# airu-board_0.net
KiCad netlist of a schematic drawn in Altium Designer
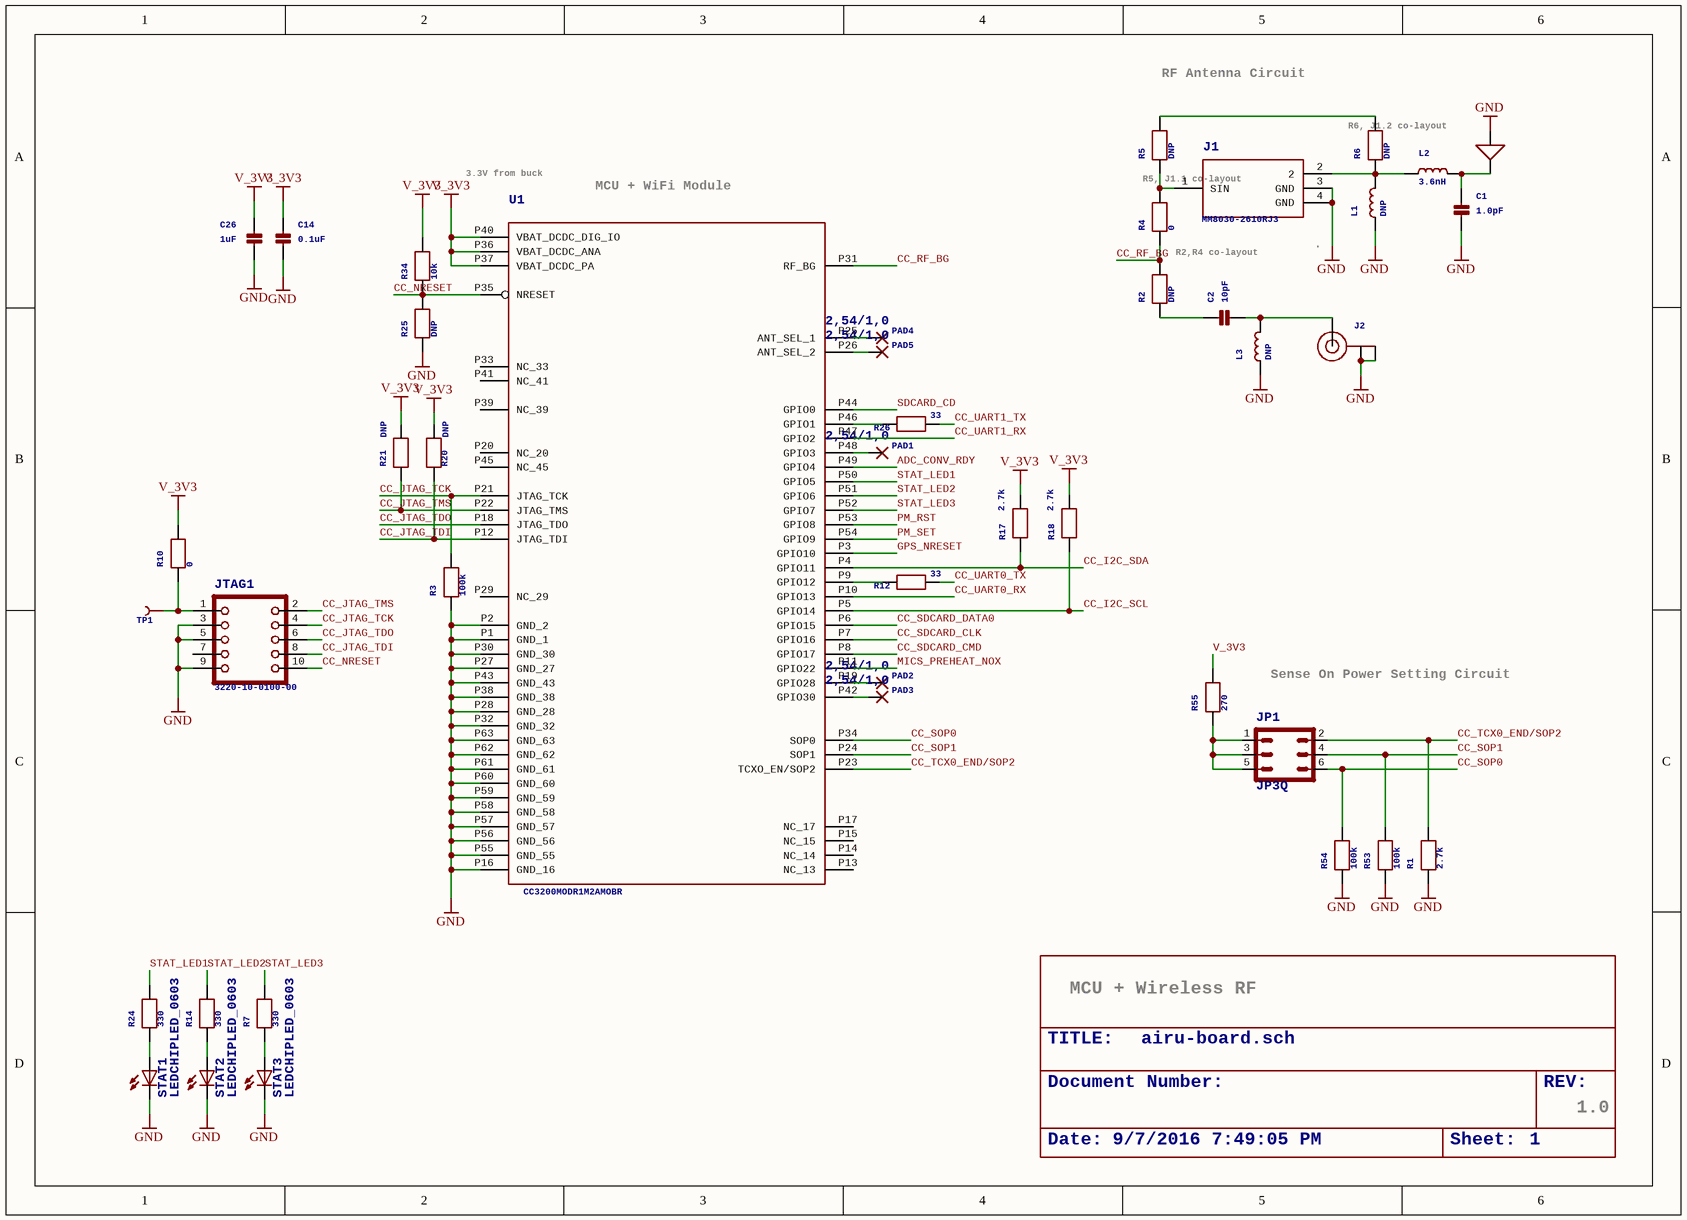
[diagram p0: airu-board_0.SchDoc]

(export (version "E")
  (design (tool "Eeschema 10.0.6"))
  (components
    (comp (ref "C1")
      (value "1.0pF")
      (footprint "0402")
      (libsource (lib "microbuilder") (part "CAP_CERAMIC0402"))
    )
    (comp (ref "C2") (value "10pF") (footprint "0402") (libsource (lib "") (part "CAP_CERAMIC0402_2")))
    (comp (ref "C14")
      (value "0.1uF")
      (footprint "0402")
      (libsource (lib "microbuilder") (part "CAP_CERAMIC0402"))
    )
    (comp (ref "C26") (value "1uF") (footprint "0402") (libsource (lib "") (part "CAP_CERAMIC0402_1")))
    (comp (ref "E1")
      (value "AH316M245001-T")
      (footprint "AH316M")
      (description "ANT BLUETOOTH W-LAN ZIGBEE WIMAX")
      (libsource (lib "yuden") (part "AH316M245001-T"))
    )
    (comp (ref "FRAME1")
      (value "FRAME_A_L")
      (description "<b>FRAME</b> A Size , 8 1/2 x 11 INCH, Landscape<p>")
      (fields
        (field (name "DATE:") "Date:")
        (field (name ">LAST_DATE_TIME") "9/7/2016 7:49:05 PM")
        (field (name "SHEET:") "Sheet:")
        (field (name ">SHEET") "1")
        (field (name "REV:") "REV:")
        (field (name "TITLE:") "TITLE:")
        (field (name "DOCUMENT NUMBER:") "Document Number:")
        (field (name ">DRAWING_NAME") "airu-board.sch")
      )
      (libsource (lib "frames") (part "FRAME_A_L"))
    )
    (comp (ref "J1")
      (value "MM8030-2610RJ3")
      (footprint "MURATA_MM8030-2610RJ3")
      (description "Conn Coaxial RCP 0Hz to 11GHz 50Ohm Solder ST SMD Gold Reel")
      (libsource (lib "MM8030-2610RJ3") (part "MM8030-2610RJ3"))
    )
    (comp (ref "J2")
      (value "U.FL-R-SMT-1(10)")
      (footprint "U.FL")
      (description "<p>U.FL Antenna Connector</p>")
      (libsource (lib "microbuilder") (part "U.FL"))
    )
    (comp (ref "JP1")
      (value "JP3Q")
      (footprint "JP3Q")
      (description "<b>JUMPER</b>")
      (libsource (lib "jumper") (part "JP3Q"))
    )
    (comp (ref "JTAG1")
      (value "3220-10-0100-00")
      (footprint "CORTEXM3_SWD10_MOLEX")
      (libsource (lib "microbuilder") (part "JTAG-CORTEXM3MOLEX"))
    )
    (comp (ref "L1")
      (value "DNP")
      (footprint "_0402")
      (libsource (lib "microbuilder") (part "INDUCTOR_0402"))
    )
    (comp (ref "L2")
      (value "3.6nH")
      (footprint "_0402")
      (libsource (lib "microbuilder") (part "INDUCTOR_0402"))
    )
    (comp (ref "L3")
      (value "DNP")
      (footprint "_0402")
      (libsource (lib "microbuilder") (part "INDUCTOR_0402"))
    )
    (comp (ref "PAD1")
      (value "2,54/1,0")
      (footprint "2,54/1,0")
      (description "<b>THROUGH-HOLE PAD</b>")
      (libsource (lib "wirepad") (part "2,54/1,0"))
    )
    (comp (ref "PAD2")
      (value "2,54/1,0")
      (footprint "2,54/1,0")
      (description "<b>THROUGH-HOLE PAD</b>")
      (libsource (lib "wirepad") (part "2,54/1,0"))
    )
    (comp (ref "PAD3")
      (value "2,54/1,0")
      (footprint "2,54/1,0")
      (description "<b>THROUGH-HOLE PAD</b>")
      (libsource (lib "wirepad") (part "2,54/1,0"))
    )
    (comp (ref "PAD4")
      (value "2,54/1,0")
      (footprint "2,54/1,0")
      (description "<b>THROUGH-HOLE PAD</b>")
      (libsource (lib "wirepad") (part "2,54/1,0"))
    )
    (comp (ref "PAD5")
      (value "2,54/1,0")
      (footprint "2,54/1,0")
      (description "<b>THROUGH-HOLE PAD</b>")
      (libsource (lib "wirepad") (part "2,54/1,0"))
    )
    (comp (ref "R1") (value "2.7k") (footprint "0402") (libsource (lib "microbuilder") (part "RESISTOR0402")))
    (comp (ref "R2") (value "DNP") (footprint "0402") (libsource (lib "microbuilder") (part "RESISTOR0402")))
    (comp (ref "R3") (value "100k") (footprint "0402") (libsource (lib "microbuilder") (part "RESISTOR0402")))
    (comp (ref "R4") (value "0") (footprint "0402") (libsource (lib "microbuilder") (part "RESISTOR0402")))
    (comp (ref "R5") (value "DNP") (footprint "0402") (libsource (lib "microbuilder") (part "RESISTOR0402")))
    (comp (ref "R6") (value "DNP") (footprint "0402") (libsource (lib "microbuilder") (part "RESISTOR0402")))
    (comp (ref "R7") (value "330") (footprint "0402") (libsource (lib "microbuilder") (part "RESISTOR0402")))
    (comp (ref "R10") (value "0") (footprint "0402") (libsource (lib "microbuilder") (part "RESISTOR0402")))
    (comp (ref "R12") (value "33") (footprint "0402") (libsource (lib "microbuilder") (part "RESISTOR0402")))
    (comp (ref "R14") (value "330") (footprint "0402") (libsource (lib "microbuilder") (part "RESISTOR0402")))
    (comp (ref "R17")
      (value "2.7k")
      (footprint "0402")
      (libsource (lib "microbuilder") (part "RESISTOR0402"))
    )
    (comp (ref "R18")
      (value "2.7k")
      (footprint "0402")
      (libsource (lib "microbuilder") (part "RESISTOR0402"))
    )
    (comp (ref "R20") (value "DNP") (footprint "0402") (libsource (lib "microbuilder") (part "RESISTOR0402")))
    (comp (ref "R21") (value "DNP") (footprint "0402") (libsource (lib "microbuilder") (part "RESISTOR0402")))
    (comp (ref "R24") (value "330") (footprint "0402") (libsource (lib "microbuilder") (part "RESISTOR0402")))
    (comp (ref "R25") (value "DNP") (footprint "0402") (libsource (lib "microbuilder") (part "RESISTOR0402")))
    (comp (ref "R26") (value "33") (footprint "0402") (libsource (lib "microbuilder") (part "RESISTOR0402")))
    (comp (ref "R34") (value "10k") (footprint "0402") (libsource (lib "microbuilder") (part "RESISTOR0402")))
    (comp (ref "R53")
      (value "100k")
      (footprint "0402")
      (libsource (lib "microbuilder") (part "RESISTOR0402"))
    )
    (comp (ref "R54")
      (value "100k")
      (footprint "0402")
      (libsource (lib "microbuilder") (part "RESISTOR0402"))
    )
    (comp (ref "R55") (value "270") (footprint "0402") (libsource (lib "microbuilder") (part "RESISTOR0402")))
    (comp (ref "STAT1")
      (value "LEDCHIPLED_0603")
      (footprint "CHIPLED_0603")
      (libsource (lib "led") (part "LEDCHIPLED_0603"))
    )
    (comp (ref "STAT2")
      (value "LEDCHIPLED_0603")
      (footprint "CHIPLED_0603")
      (libsource (lib "led") (part "LEDCHIPLED_0603"))
    )
    (comp (ref "STAT3")
      (value "LEDCHIPLED_0603")
      (footprint "CHIPLED_0603")
      (libsource (lib "led") (part "LEDCHIPLED_0603"))
    )
    (comp (ref "TP1")
      (value "TEST-POINT2")
      (footprint "PAD.02X.02")
      (description "Bare copper test points for troubleshooting or ICT")
      (libsource (lib "SparkFun-Passives") (part "TEST-POINT2"))
    )
    (comp (ref "U1")
      (value "CC3200MODR1M2AMOBR")
      (footprint "CC3200MOD")
      (libsource (lib "texas") (part "CC3200MOD"))
    )
  )
  (nets
    (net (code "1") (name "/ADC_CONV_RDY") (class "Default")
      (node (ref "U1") (pin "P49") (pinfunction "GPIO4_P49") (pintype "passive"))
    )
    (net (code "2") (name "/CC_I2C_SCL") (class "Default")
      (node (ref "R18") (pin "1") (pinfunction "1_1") (pintype "passive"))
      (node (ref "U1") (pin "P5") (pinfunction "GPIO14_P5") (pintype "passive"))
    )
    (net (code "3") (name "/CC_I2C_SDA") (class "Default")
      (node (ref "R17") (pin "1") (pinfunction "1_1") (pintype "passive"))
      (node (ref "U1") (pin "P4") (pinfunction "GPIO11_P4") (pintype "passive"))
    )
    (net (code "4") (name "/CC_JTAG_TCK") (class "Default")
      (node (ref "JTAG1") (pin "4") (pinfunction "4_4") (pintype "passive"))
      (node (ref "R3") (pin "2") (pinfunction "2_2") (pintype "passive"))
      (node (ref "U1") (pin "P21") (pinfunction "JTAG_TCK_P21") (pintype "passive"))
    )
    (net (code "5") (name "/CC_JTAG_TDI") (class "Default")
      (node (ref "JTAG1") (pin "8") (pinfunction "8_8") (pintype "passive"))
      (node (ref "R20") (pin "1") (pinfunction "1_1") (pintype "passive"))
      (node (ref "U1") (pin "P12") (pinfunction "JTAG_TDI_P12") (pintype "passive"))
    )
    (net (code "6") (name "/CC_JTAG_TDO") (class "Default")
      (node (ref "JTAG1") (pin "6") (pinfunction "6_6") (pintype "passive"))
      (node (ref "U1") (pin "P18") (pinfunction "JTAG_TDO_P18") (pintype "passive"))
    )
    (net (code "7") (name "/CC_JTAG_TMS") (class "Default")
      (node (ref "JTAG1") (pin "2") (pinfunction "2_2") (pintype "passive"))
      (node (ref "R21") (pin "1") (pinfunction "1_1") (pintype "passive"))
      (node (ref "U1") (pin "P22") (pinfunction "JTAG_TMS_P22") (pintype "passive"))
    )
    (net (code "8") (name "/CC_NRESET") (class "Default")
      (node (ref "JTAG1") (pin "10") (pinfunction "10_10") (pintype "passive"))
      (node (ref "R25") (pin "2") (pinfunction "2_2") (pintype "passive"))
      (node (ref "R34") (pin "1") (pinfunction "1_1") (pintype "passive"))
      (node (ref "U1") (pin "P35") (pinfunction "NRESET_P35") (pintype "passive"))
    )
    (net (code "9") (name "/CC_RF_BG") (class "Default")
      (node (ref "R2") (pin "2") (pinfunction "2_2") (pintype "passive"))
      (node (ref "R4") (pin "1") (pinfunction "1_1") (pintype "passive"))
      (node (ref "U1") (pin "P31") (pinfunction "RF_BG_P31") (pintype "passive"))
    )
    (net (code "10") (name "/CC_SDCARD_CLK") (class "Default")
      (node (ref "U1") (pin "P7") (pinfunction "GPIO16_P7") (pintype "passive"))
    )
    (net (code "11") (name "/CC_SDCARD_CMD") (class "Default")
      (node (ref "U1") (pin "P8") (pinfunction "GPIO17_P8") (pintype "passive"))
    )
    (net (code "12") (name "/CC_SDCARD_DATA0") (class "Default")
      (node (ref "U1") (pin "P6") (pinfunction "GPIO15_P6") (pintype "passive"))
    )
    (net (code "13") (name "/CC_SOP0") (class "Default")
      (node (ref "JP1") (pin "6") (pinfunction "6_6") (pintype "passive"))
      (node (ref "R54") (pin "2") (pinfunction "2_2") (pintype "passive"))
      (node (ref "U1") (pin "P34") (pinfunction "SOP0_P34") (pintype "passive"))
    )
    (net (code "14") (name "/CC_SOP1") (class "Default")
      (node (ref "JP1") (pin "4") (pinfunction "4_4") (pintype "passive"))
      (node (ref "R53") (pin "2") (pinfunction "2_2") (pintype "passive"))
      (node (ref "U1") (pin "P24") (pinfunction "SOP1_P24") (pintype "passive"))
    )
    (net (code "15") (name "/CC_TCX0_END{slash}SOP2") (class "Default")
      (node (ref "JP1") (pin "2") (pinfunction "2_2") (pintype "passive"))
      (node (ref "R1") (pin "2") (pinfunction "2_2") (pintype "passive"))
      (node (ref "U1") (pin "P23") (pinfunction "TCXO_EN/SOP2_P23") (pintype "passive"))
    )
    (net (code "16") (name "/CC_UART0_RX") (class "Default")
      (node (ref "U1") (pin "P10") (pinfunction "GPIO13_P10") (pintype "passive"))
    )
    (net (code "17") (name "/CC_UART0_TX") (class "Default")
      (node (ref "R12") (pin "2") (pinfunction "2_2") (pintype "passive"))
    )
    (net (code "18") (name "/CC_UART1_RX") (class "Default")
      (node (ref "U1") (pin "P47") (pinfunction "GPIO2_P47") (pintype "passive"))
    )
    (net (code "19") (name "/CC_UART1_TX") (class "Default")
      (node (ref "R26") (pin "2") (pinfunction "2_2") (pintype "passive"))
    )
    (net (code "20") (name "/GPS_NRESET") (class "Default")
      (node (ref "U1") (pin "P3") (pinfunction "GPIO10_P3") (pintype "passive"))
    )
    (net (code "21") (name "/MICS_PREHEAT_NOX") (class "Default")
      (node (ref "U1") (pin "P11") (pinfunction "GPIO22_P11") (pintype "passive"))
    )
    (net (code "22") (name "/PM_RST") (class "Default")
      (node (ref "U1") (pin "P53") (pinfunction "GPIO8_P53") (pintype "passive"))
    )
    (net (code "23") (name "/PM_SET") (class "Default")
      (node (ref "U1") (pin "P54") (pinfunction "GPIO9_P54") (pintype "passive"))
    )
    (net (code "24") (name "/SDCARD_CD") (class "Default")
      (node (ref "U1") (pin "P44") (pinfunction "GPIO0_P44") (pintype "passive"))
    )
    (net (code "25") (name "/STAT_LED1") (class "Default")
      (node (ref "R24") (pin "2") (pinfunction "2_2") (pintype "passive"))
      (node (ref "U1") (pin "P50") (pinfunction "GPIO5_P50") (pintype "passive"))
    )
    (net (code "26") (name "/STAT_LED2") (class "Default")
      (node (ref "R14") (pin "2") (pinfunction "2_2") (pintype "passive"))
      (node (ref "U1") (pin "P51") (pinfunction "GPIO6_P51") (pintype "passive"))
    )
    (net (code "27") (name "/STAT_LED3") (class "Default")
      (node (ref "R7") (pin "2") (pinfunction "2_2") (pintype "passive"))
      (node (ref "U1") (pin "P52") (pinfunction "GPIO7_P52") (pintype "passive"))
    )
    (net (code "28") (name "GND") (class "Default")
      (node (ref "C1") (pin "2") (pinfunction "P$2_2") (pintype "passive"))
      (node (ref "C14") (pin "2") (pinfunction "P$2_2") (pintype "passive"))
      (node (ref "C26") (pin "2") (pinfunction "P$2_2") (pintype "passive"))
      (node (ref "E1") (pin "P$2") (pinfunction "P$2_P$2") (pintype "power_in"))
      (node (ref "J1") (pin "3") (pinfunction "GND_3") (pintype "power_in"))
      (node (ref "J1") (pin "4") (pinfunction "GND_4") (pintype "power_in"))
      (node (ref "J2") (pin "1") (pinfunction "GND_1") (pintype "passive"))
      (node (ref "J2") (pin "2") (pinfunction "GND_2") (pintype "passive"))
      (node (ref "JTAG1") (pin "3") (pinfunction "3_3") (pintype "passive"))
      (node (ref "JTAG1") (pin "5") (pinfunction "5_5") (pintype "passive"))
      (node (ref "JTAG1") (pin "9") (pinfunction "9_9") (pintype "passive"))
      (node (ref "L1") (pin "1") (pinfunction "1_1") (pintype "passive"))
      (node (ref "L3") (pin "1") (pinfunction "1_1") (pintype "passive"))
      (node (ref "R1") (pin "1") (pinfunction "1_1") (pintype "passive"))
      (node (ref "R25") (pin "1") (pinfunction "1_1") (pintype "passive"))
      (node (ref "R3") (pin "1") (pinfunction "1_1") (pintype "passive"))
      (node (ref "R53") (pin "1") (pinfunction "1_1") (pintype "passive"))
      (node (ref "R54") (pin "1") (pinfunction "1_1") (pintype "passive"))
      (node (ref "STAT1") (pin "C") (pinfunction "C_C") (pintype "passive"))
      (node (ref "STAT2") (pin "C") (pinfunction "C_C") (pintype "passive"))
      (node (ref "STAT3") (pin "C") (pinfunction "C_C") (pintype "passive"))
      (node (ref "U1") (pin "P1") (pinfunction "GND_1_P1") (pintype "passive"))
      (node (ref "U1") (pin "P16") (pinfunction "GND_16_P16") (pintype "passive"))
      (node (ref "U1") (pin "P2") (pinfunction "GND_2_P2") (pintype "passive"))
      (node (ref "U1") (pin "P27") (pinfunction "GND_27_P27") (pintype "passive"))
      (node (ref "U1") (pin "P28") (pinfunction "GND_28_P28") (pintype "passive"))
      (node (ref "U1") (pin "P30") (pinfunction "GND_30_P30") (pintype "passive"))
      (node (ref "U1") (pin "P32") (pinfunction "GND_32_P32") (pintype "passive"))
      (node (ref "U1") (pin "P38") (pinfunction "GND_38_P38") (pintype "passive"))
      (node (ref "U1") (pin "P43") (pinfunction "GND_43_P43") (pintype "passive"))
      (node (ref "U1") (pin "P55") (pinfunction "GND_55_P55") (pintype "passive"))
      (node (ref "U1") (pin "P56") (pinfunction "GND_56_P56") (pintype "passive"))
      (node (ref "U1") (pin "P57") (pinfunction "GND_57_P57") (pintype "passive"))
      (node (ref "U1") (pin "P58") (pinfunction "GND_58_P58") (pintype "passive"))
      (node (ref "U1") (pin "P59") (pinfunction "GND_59_P59") (pintype "passive"))
      (node (ref "U1") (pin "P60") (pinfunction "GND_60_P60") (pintype "passive"))
      (node (ref "U1") (pin "P61") (pinfunction "GND_61_P61") (pintype "passive"))
      (node (ref "U1") (pin "P62") (pinfunction "GND_62_P62") (pintype "passive"))
      (node (ref "U1") (pin "P63") (pinfunction "GND_63_P63") (pintype "passive"))
    )
    (net (code "29") (name "Net-(C1-P$1)") (class "Default")
      (node (ref "C1") (pin "1") (pinfunction "P$1_1") (pintype "passive"))
      (node (ref "E1") (pin "P$1") (pinfunction "P$1_P$1") (pintype "passive"))
      (node (ref "L2") (pin "2") (pinfunction "2_2") (pintype "passive"))
    )
    (net (code "30") (name "Net-(C2-P$1)") (class "Default")
      (node (ref "C2") (pin "1") (pinfunction "P$1_1") (pintype "passive"))
      (node (ref "R2") (pin "1") (pinfunction "1_1") (pintype "passive"))
    )
    (net (code "31") (name "Net-(C2-P$2)") (class "Default")
      (node (ref "C2") (pin "2") (pinfunction "P$2_2") (pintype "passive"))
      (node (ref "J2") (pin "3") (pinfunction "SIGNAL_3") (pintype "passive"))
      (node (ref "L3") (pin "2") (pinfunction "2_2") (pintype "passive"))
    )
    (net (code "32") (name "Net-(J1-Pad2)") (class "Default")
      (node (ref "J1") (pin "2") (pinfunction "2_2") (pintype "passive"))
      (node (ref "L1") (pin "2") (pinfunction "2_2") (pintype "passive"))
      (node (ref "L2") (pin "1") (pinfunction "1_1") (pintype "passive"))
      (node (ref "R6") (pin "1") (pinfunction "1_1") (pintype "passive"))
    )
    (net (code "33") (name "Net-(J1-SIN)") (class "Default")
      (node (ref "J1") (pin "1") (pinfunction "SIN_1") (pintype "passive"))
      (node (ref "R4") (pin "2") (pinfunction "2_2") (pintype "passive"))
      (node (ref "R5") (pin "1") (pinfunction "1_1") (pintype "passive"))
    )
    (net (code "34") (name "Net-(JP1-Pad1)") (class "Default")
      (node (ref "JP1") (pin "1") (pinfunction "1_1") (pintype "passive"))
      (node (ref "JP1") (pin "3") (pinfunction "3_3") (pintype "passive"))
      (node (ref "JP1") (pin "5") (pinfunction "5_5") (pintype "passive"))
      (node (ref "R55") (pin "1") (pinfunction "1_1") (pintype "passive"))
    )
    (net (code "35") (name "Net-(PAD1-P)") (class "Default")
      (node (ref "PAD1") (pin "1") (pinfunction "P_1") (pintype "passive"))
      (node (ref "U1") (pin "P48") (pinfunction "GPIO3_P48") (pintype "passive"))
    )
    (net (code "36") (name "Net-(PAD2-P)") (class "Default")
      (node (ref "PAD2") (pin "1") (pinfunction "P_1") (pintype "passive"))
      (node (ref "U1") (pin "P19") (pinfunction "GPIO28_P19") (pintype "passive"))
    )
    (net (code "37") (name "Net-(PAD3-P)") (class "Default")
      (node (ref "PAD3") (pin "1") (pinfunction "P_1") (pintype "passive"))
      (node (ref "U1") (pin "P42") (pinfunction "GPIO30_P42") (pintype "passive"))
    )
    (net (code "38") (name "Net-(PAD4-P)") (class "Default")
      (node (ref "PAD4") (pin "1") (pinfunction "P_1") (pintype "passive"))
      (node (ref "U1") (pin "P25") (pinfunction "ANT_SEL_1_P25") (pintype "passive"))
    )
    (net (code "39") (name "Net-(PAD5-P)") (class "Default")
      (node (ref "PAD5") (pin "1") (pinfunction "P_1") (pintype "passive"))
      (node (ref "U1") (pin "P26") (pinfunction "ANT_SEL_2_P26") (pintype "passive"))
    )
    (net (code "40") (name "Net-(R5-Pad2)") (class "Default")
      (node (ref "R5") (pin "2") (pinfunction "2_2") (pintype "passive"))
      (node (ref "R6") (pin "2") (pinfunction "2_2") (pintype "passive"))
    )
    (net (code "41") (name "Net-(R7-Pad1)") (class "Default")
      (node (ref "R7") (pin "1") (pinfunction "1_1") (pintype "passive"))
      (node (ref "STAT3") (pin "A") (pinfunction "A_A") (pintype "passive"))
    )
    (net (code "42") (name "Net-(R14-Pad1)") (class "Default")
      (node (ref "R14") (pin "1") (pinfunction "1_1") (pintype "passive"))
      (node (ref "STAT2") (pin "A") (pinfunction "A_A") (pintype "passive"))
    )
    (net (code "43") (name "Net-(R24-Pad1)") (class "Default")
      (node (ref "R24") (pin "1") (pinfunction "1_1") (pintype "passive"))
      (node (ref "STAT1") (pin "A") (pinfunction "A_A") (pintype "passive"))
    )
    (net (code "44") (name "Net-(TP1-1)") (class "Default")
      (node (ref "JTAG1") (pin "1") (pinfunction "1_1") (pintype "passive"))
      (node (ref "R10") (pin "1") (pinfunction "1_1") (pintype "passive"))
      (node (ref "TP1") (pin "P$1") (pinfunction "1_P$1") (pintype "passive"))
    )
    (net (code "45") (name "Net-(U1-GPIO1)") (class "Default")
      (node (ref "R26") (pin "1") (pinfunction "1_1") (pintype "passive"))
      (node (ref "U1") (pin "P46") (pinfunction "GPIO1_P46") (pintype "passive"))
    )
    (net (code "46") (name "Net-(U1-GPIO12)") (class "Default")
      (node (ref "R12") (pin "1") (pinfunction "1_1") (pintype "passive"))
      (node (ref "U1") (pin "P9") (pinfunction "GPIO12_P9") (pintype "passive"))
    )
    (net (code "47") (name "V_3V3") (class "Default")
      (node (ref "C14") (pin "1") (pinfunction "P$1_1") (pintype "passive"))
      (node (ref "C26") (pin "1") (pinfunction "P$1_1") (pintype "passive"))
      (node (ref "R10") (pin "2") (pinfunction "2_2") (pintype "passive"))
      (node (ref "R17") (pin "2") (pinfunction "2_2") (pintype "passive"))
      (node (ref "R18") (pin "2") (pinfunction "2_2") (pintype "passive"))
      (node (ref "R20") (pin "2") (pinfunction "2_2") (pintype "passive"))
      (node (ref "R21") (pin "2") (pinfunction "2_2") (pintype "passive"))
      (node (ref "R34") (pin "2") (pinfunction "2_2") (pintype "passive"))
      (node (ref "R55") (pin "2") (pinfunction "2_2") (pintype "passive"))
      (node (ref "U1") (pin "P36") (pinfunction "VBAT_DCDC_ANA_P36") (pintype "power_in"))
      (node (ref "U1") (pin "P37") (pinfunction "VBAT_DCDC_PA_P37") (pintype "power_in"))
      (node (ref "U1") (pin "P40") (pinfunction "VBAT_DCDC_DIG_IO_P40") (pintype "power_in"))
    )
    (net (code "48") (name "unconnected-(JTAG1-Pad7)") (class "Default")
      (node (ref "JTAG1") (pin "7") (pinfunction "7_7") (pintype "passive"))
    )
    (net (code "49") (name "unconnected-(U1-NC_13-PadP13)") (class "Default")
      (node (ref "U1") (pin "P13") (pinfunction "NC_13_P13") (pintype "passive"))
    )
    (net (code "50") (name "unconnected-(U1-NC_14-PadP14)") (class "Default")
      (node (ref "U1") (pin "P14") (pinfunction "NC_14_P14") (pintype "passive"))
    )
    (net (code "51") (name "unconnected-(U1-NC_15-PadP15)") (class "Default")
      (node (ref "U1") (pin "P15") (pinfunction "NC_15_P15") (pintype "passive"))
    )
    (net (code "52") (name "unconnected-(U1-NC_17-PadP17)") (class "Default")
      (node (ref "U1") (pin "P17") (pinfunction "NC_17_P17") (pintype "passive"))
    )
    (net (code "53") (name "unconnected-(U1-NC_20-PadP20)") (class "Default")
      (node (ref "U1") (pin "P20") (pinfunction "NC_20_P20") (pintype "passive"))
    )
    (net (code "54") (name "unconnected-(U1-NC_29-PadP29)") (class "Default")
      (node (ref "U1") (pin "P29") (pinfunction "NC_29_P29") (pintype "passive"))
    )
    (net (code "55") (name "unconnected-(U1-NC_33-PadP33)") (class "Default")
      (node (ref "U1") (pin "P33") (pinfunction "NC_33_P33") (pintype "passive"))
    )
    (net (code "56") (name "unconnected-(U1-NC_39-PadP39)") (class "Default")
      (node (ref "U1") (pin "P39") (pinfunction "NC_39_P39") (pintype "passive"))
    )
    (net (code "57") (name "unconnected-(U1-NC_41-PadP41)") (class "Default")
      (node (ref "U1") (pin "P41") (pinfunction "NC_41_P41") (pintype "passive"))
    )
    (net (code "58") (name "unconnected-(U1-NC_45-PadP45)") (class "Default")
      (node (ref "U1") (pin "P45") (pinfunction "NC_45_P45") (pintype "passive"))
    )
  )
)
